# STM32_H750_POWER.net
KiCad netlist of a schematic drawn in Altium Designer
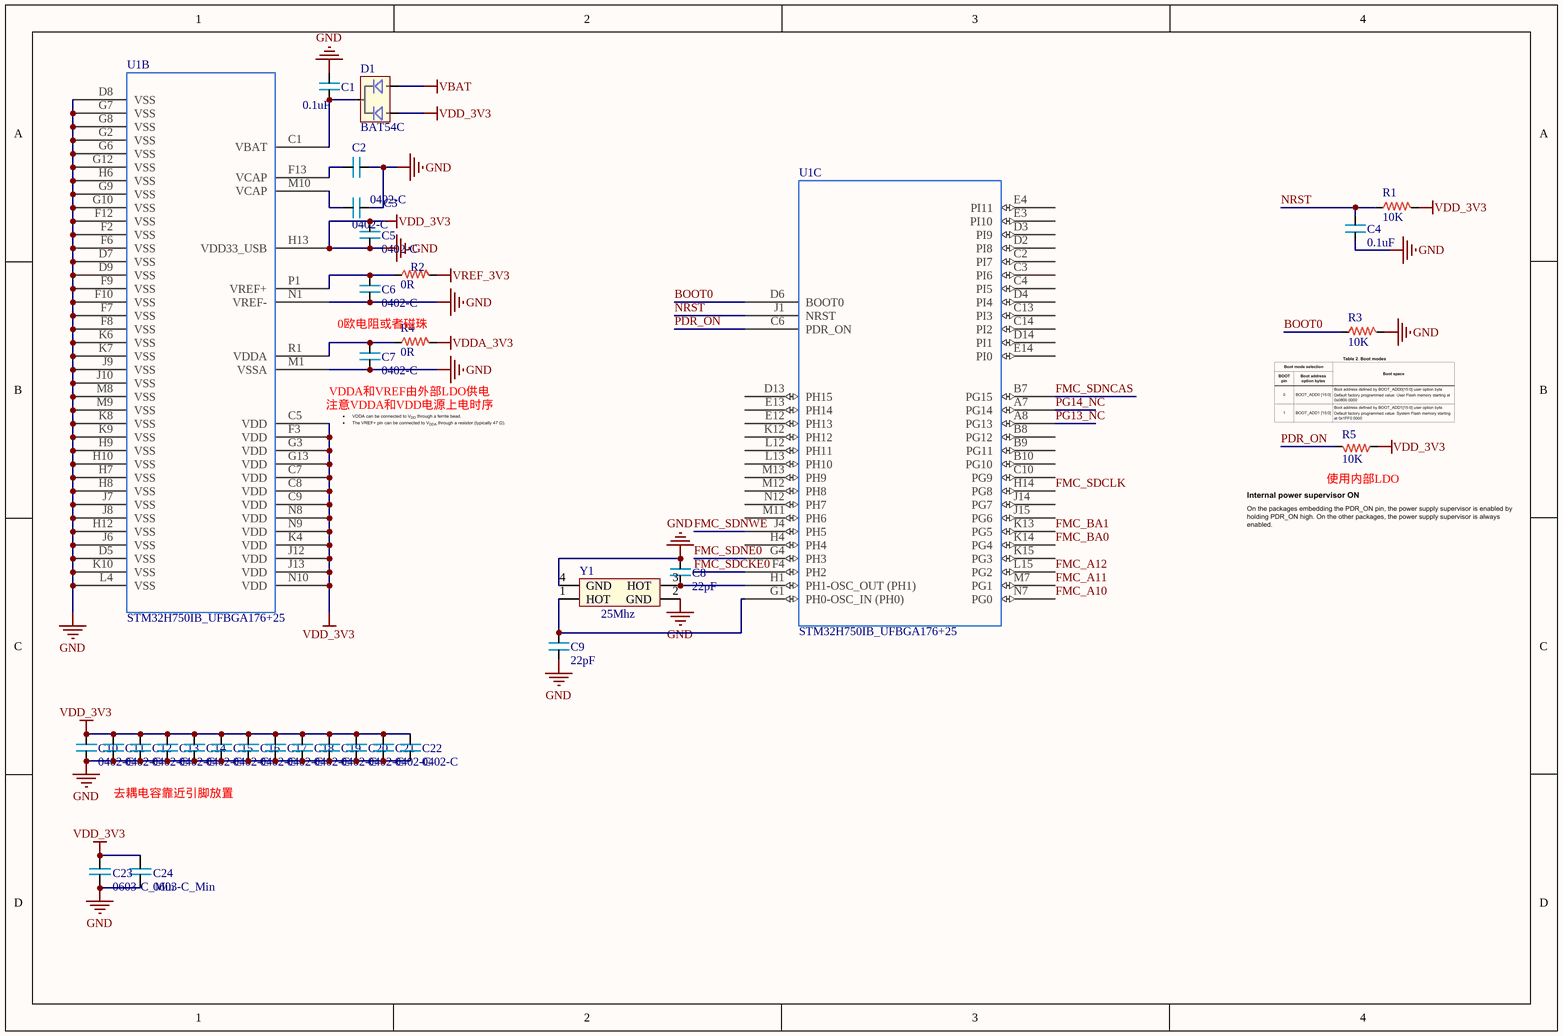
[diagram p0: STM32_H750_POWER.SchDoc]

(export (version "E")
  (design (tool "Eeschema 10.0.6"))
  (components
    (comp (ref "C1") (value "0.1uF") (footprint "0402") (libsource (lib "mcu") (part "0402-C")))
    (comp (ref "C2") (value "0402-C") (footprint "0402") (libsource (lib "mcu") (part "0402-C")))
    (comp (ref "C3") (value "0402-C") (footprint "0402") (libsource (lib "mcu") (part "0402-C")))
    (comp (ref "C4") (value "0.1uF") (footprint "0402") (libsource (lib "mcu") (part "0402-C")))
    (comp (ref "C5") (value "0402-C") (footprint "0402") (libsource (lib "mcu") (part "0402-C")))
    (comp (ref "C6") (value "0402-C") (footprint "0402") (libsource (lib "mcu") (part "0402-C")))
    (comp (ref "C7") (value "0402-C") (footprint "0402") (libsource (lib "mcu") (part "0402-C")))
    (comp (ref "C8") (value "22pF") (footprint "0402") (libsource (lib "mcu") (part "0402-C")))
    (comp (ref "C9") (value "22pF") (footprint "0402") (libsource (lib "mcu") (part "0402-C")))
    (comp (ref "C10") (value "0402-C") (footprint "0402") (libsource (lib "mcu") (part "0402-C")))
    (comp (ref "C11") (value "0402-C") (footprint "0402") (libsource (lib "mcu") (part "0402-C")))
    (comp (ref "C12") (value "0402-C") (footprint "0402") (libsource (lib "mcu") (part "0402-C")))
    (comp (ref "C13") (value "0402-C") (footprint "0402") (libsource (lib "mcu") (part "0402-C")))
    (comp (ref "C14") (value "0402-C") (footprint "0402") (libsource (lib "mcu") (part "0402-C")))
    (comp (ref "C15") (value "0402-C") (footprint "0402") (libsource (lib "mcu") (part "0402-C")))
    (comp (ref "C16") (value "0402-C") (footprint "0402") (libsource (lib "mcu") (part "0402-C")))
    (comp (ref "C17") (value "0402-C") (footprint "0402") (libsource (lib "mcu") (part "0402-C")))
    (comp (ref "C18") (value "0402-C") (footprint "0402") (libsource (lib "mcu") (part "0402-C")))
    (comp (ref "C19") (value "0402-C") (footprint "0402") (libsource (lib "mcu") (part "0402-C")))
    (comp (ref "C20") (value "0402-C") (footprint "0402") (libsource (lib "mcu") (part "0402-C")))
    (comp (ref "C21") (value "0402-C") (footprint "0402") (libsource (lib "mcu") (part "0402-C")))
    (comp (ref "C22") (value "0402-C") (footprint "0402") (libsource (lib "mcu") (part "0402-C")))
    (comp (ref "C23")
      (value "0603-C_Min")
      (footprint "0603P - 2")
      (libsource (lib "0718") (part "0603-C_Min"))
    )
    (comp (ref "C24")
      (value "0603-C_Min")
      (footprint "0603P - 2")
      (libsource (lib "0718") (part "0603-C_Min"))
    )
    (comp (ref "D1")
      (value "BAT54C")
      (footprint "SOT23-3")
      (description "双肖特基二极管")
      (libsource (lib "0718") (part "BAT54C"))
    )
    (comp (ref "R1") (value "10K") (footprint "0402") (libsource (lib "mcu") (part "0402-R")))
    (comp (ref "R2") (value "0R") (footprint "0402") (libsource (lib "mcu") (part "0402-R")))
    (comp (ref "R3") (value "10K") (footprint "0402") (libsource (lib "mcu") (part "0402-R")))
    (comp (ref "R4") (value "0R") (footprint "0402") (libsource (lib "mcu") (part "0402-R")))
    (comp (ref "R5") (value "10K") (footprint "0402") (libsource (lib "mcu") (part "0402-R")))
    (comp (ref "U1")
      (value "STM32H750IB_UFBGA176+25")
      (footprint "mcu:STM32H750IB_UFBGA176+25")
      (libsource (lib "") (part "STM32H750IB_UFBGA176+25_1"))
    )
    (comp (ref "Y1")
      (value "25Mhz")
      (footprint "XTAL3225")
      (description "3225贴片无源晶振")
      (libsource (lib "0718") (part "XTAL_3225"))
    )
  )
  (nets
    (net (code "1") (name "/BOOT0") (class "Default")
      (node (ref "R3") (pin "1") (pinfunction "1_1") (pintype "passive"))
      (node (ref "U1") (pin "D6") (pinfunction "BOOT0_D6") (pintype "power_in"))
    )
    (net (code "2") (name "/FMC_A10") (class "Default")
      (node (ref "U1") (pin "N7") (pinfunction "PG0_N7") (pintype "bidirectional"))
    )
    (net (code "3") (name "/FMC_A11") (class "Default")
      (node (ref "U1") (pin "M7") (pinfunction "PG1_M7") (pintype "bidirectional"))
    )
    (net (code "4") (name "/FMC_A12") (class "Default")
      (node (ref "U1") (pin "L15") (pinfunction "PG2_L15") (pintype "bidirectional"))
    )
    (net (code "5") (name "/FMC_BA0") (class "Default")
      (node (ref "U1") (pin "K14") (pinfunction "PG4_K14") (pintype "bidirectional"))
    )
    (net (code "6") (name "/FMC_BA1") (class "Default")
      (node (ref "U1") (pin "K13") (pinfunction "PG5_K13") (pintype "bidirectional"))
    )
    (net (code "7") (name "/FMC_SDCKE0") (class "Default")
      (node (ref "U1") (pin "F4") (pinfunction "PH2_F4") (pintype "bidirectional"))
    )
    (net (code "8") (name "/FMC_SDCLK") (class "Default")
      (node (ref "U1") (pin "H14") (pinfunction "PG8_H14") (pintype "bidirectional"))
    )
    (net (code "9") (name "/FMC_SDNCAS") (class "Default")
      (node (ref "U1") (pin "B7") (pinfunction "PG15_B7") (pintype "bidirectional"))
    )
    (net (code "10") (name "/FMC_SDNE0") (class "Default")
      (node (ref "U1") (pin "G4") (pinfunction "PH3_G4") (pintype "bidirectional"))
    )
    (net (code "11") (name "/FMC_SDNWE") (class "Default")
      (node (ref "U1") (pin "J4") (pinfunction "PH5_J4") (pintype "bidirectional"))
    )
    (net (code "12") (name "/NRST") (class "Default")
      (node (ref "C4") (pin "2") (pinfunction "2_2") (pintype "passive"))
      (node (ref "R1") (pin "1") (pinfunction "1_1") (pintype "passive"))
      (node (ref "U1") (pin "J1") (pinfunction "NRST_J1") (pintype "power_in"))
    )
    (net (code "13") (name "/PDR_ON") (class "Default")
      (node (ref "R5") (pin "2") (pinfunction "2_2") (pintype "passive"))
      (node (ref "U1") (pin "C6") (pinfunction "PDR_ON_C6") (pintype "power_in"))
    )
    (net (code "14") (name "/PG13_NC") (class "Default")
      (node (ref "U1") (pin "A8") (pinfunction "PG13_A8") (pintype "bidirectional"))
    )
    (net (code "15") (name "/PG14_NC") (class "Default")
      (node (ref "U1") (pin "A7") (pinfunction "PG14_A7") (pintype "bidirectional"))
    )
    (net (code "16") (name "GND") (class "Default")
      (node (ref "C1") (pin "2") (pinfunction "2_2") (pintype "passive"))
      (node (ref "C10") (pin "1") (pinfunction "1_1") (pintype "passive"))
      (node (ref "C10") (pin "2") (pinfunction "2_2") (pintype "passive"))
      (node (ref "C11") (pin "1") (pinfunction "1_1") (pintype "passive"))
      (node (ref "C11") (pin "2") (pinfunction "2_2") (pintype "passive"))
      (node (ref "C12") (pin "1") (pinfunction "1_1") (pintype "passive"))
      (node (ref "C12") (pin "2") (pinfunction "2_2") (pintype "passive"))
      (node (ref "C13") (pin "1") (pinfunction "1_1") (pintype "passive"))
      (node (ref "C13") (pin "2") (pinfunction "2_2") (pintype "passive"))
      (node (ref "C14") (pin "1") (pinfunction "1_1") (pintype "passive"))
      (node (ref "C14") (pin "2") (pinfunction "2_2") (pintype "passive"))
      (node (ref "C15") (pin "1") (pinfunction "1_1") (pintype "passive"))
      (node (ref "C15") (pin "2") (pinfunction "2_2") (pintype "passive"))
      (node (ref "C16") (pin "1") (pinfunction "1_1") (pintype "passive"))
      (node (ref "C16") (pin "2") (pinfunction "2_2") (pintype "passive"))
      (node (ref "C17") (pin "1") (pinfunction "1_1") (pintype "passive"))
      (node (ref "C17") (pin "2") (pinfunction "2_2") (pintype "passive"))
      (node (ref "C18") (pin "1") (pinfunction "1_1") (pintype "passive"))
      (node (ref "C18") (pin "2") (pinfunction "2_2") (pintype "passive"))
      (node (ref "C19") (pin "1") (pinfunction "1_1") (pintype "passive"))
      (node (ref "C19") (pin "2") (pinfunction "2_2") (pintype "passive"))
      (node (ref "C2") (pin "1") (pinfunction "1_1") (pintype "passive"))
      (node (ref "C20") (pin "1") (pinfunction "1_1") (pintype "passive"))
      (node (ref "C20") (pin "2") (pinfunction "2_2") (pintype "passive"))
      (node (ref "C21") (pin "1") (pinfunction "1_1") (pintype "passive"))
      (node (ref "C21") (pin "2") (pinfunction "2_2") (pintype "passive"))
      (node (ref "C22") (pin "1") (pinfunction "1_1") (pintype "passive"))
      (node (ref "C22") (pin "2") (pinfunction "2_2") (pintype "passive"))
      (node (ref "C23") (pin "1") (pinfunction "1_1") (pintype "passive"))
      (node (ref "C23") (pin "2") (pinfunction "2_2") (pintype "passive"))
      (node (ref "C24") (pin "1") (pinfunction "1_1") (pintype "passive"))
      (node (ref "C24") (pin "2") (pinfunction "2_2") (pintype "passive"))
      (node (ref "C3") (pin "2") (pinfunction "2_2") (pintype "passive"))
      (node (ref "C4") (pin "1") (pinfunction "1_1") (pintype "passive"))
      (node (ref "C5") (pin "1") (pinfunction "1_1") (pintype "passive"))
      (node (ref "C5") (pin "2") (pinfunction "2_2") (pintype "passive"))
      (node (ref "C6") (pin "1") (pinfunction "1_1") (pintype "passive"))
      (node (ref "C7") (pin "1") (pinfunction "1_1") (pintype "passive"))
      (node (ref "C8") (pin "2") (pinfunction "2_2") (pintype "passive"))
      (node (ref "C9") (pin "2") (pinfunction "2_2") (pintype "passive"))
      (node (ref "D1") (pin "1") (pintype "passive"))
      (node (ref "R1") (pin "2") (pinfunction "2_2") (pintype "passive"))
      (node (ref "R3") (pin "2") (pinfunction "2_2") (pintype "passive"))
      (node (ref "R5") (pin "1") (pinfunction "1_1") (pintype "passive"))
      (node (ref "U1") (pin "C5") (pinfunction "VDD_C5") (pintype "power_in"))
      (node (ref "U1") (pin "C7") (pinfunction "VDD_C7") (pintype "power_in"))
      (node (ref "U1") (pin "C8") (pinfunction "VDD_C8") (pintype "power_in"))
      (node (ref "U1") (pin "C9") (pinfunction "VDD_C9") (pintype "power_in"))
      (node (ref "U1") (pin "D5") (pinfunction "VSS_D5") (pintype "power_in"))
      (node (ref "U1") (pin "D7") (pinfunction "VSS_D7") (pintype "power_in"))
      (node (ref "U1") (pin "D8") (pinfunction "VSS_D8") (pintype "power_in"))
      (node (ref "U1") (pin "D9") (pinfunction "VSS_D9") (pintype "power_in"))
      (node (ref "U1") (pin "F10") (pinfunction "VSS_F10") (pintype "power_in"))
      (node (ref "U1") (pin "F12") (pinfunction "VSS_F12") (pintype "power_in"))
      (node (ref "U1") (pin "F2") (pinfunction "VSS_F2") (pintype "power_in"))
      (node (ref "U1") (pin "F3") (pinfunction "VDD_F3") (pintype "power_in"))
      (node (ref "U1") (pin "F6") (pinfunction "VSS_F6") (pintype "power_in"))
      (node (ref "U1") (pin "F7") (pinfunction "VSS_F7") (pintype "power_in"))
      (node (ref "U1") (pin "F8") (pinfunction "VSS_F8") (pintype "power_in"))
      (node (ref "U1") (pin "F9") (pinfunction "VSS_F9") (pintype "power_in"))
      (node (ref "U1") (pin "G10") (pinfunction "VSS_G10") (pintype "power_in"))
      (node (ref "U1") (pin "G12") (pinfunction "VSS_G12") (pintype "power_in"))
      (node (ref "U1") (pin "G13") (pinfunction "VDD_G13") (pintype "power_in"))
      (node (ref "U1") (pin "G2") (pinfunction "VSS_G2") (pintype "power_in"))
      (node (ref "U1") (pin "G3") (pinfunction "VDD_G3") (pintype "power_in"))
      (node (ref "U1") (pin "G6") (pinfunction "VSS_G6") (pintype "power_in"))
      (node (ref "U1") (pin "G7") (pinfunction "VSS_G7") (pintype "power_in"))
      (node (ref "U1") (pin "G8") (pinfunction "VSS_G8") (pintype "power_in"))
      (node (ref "U1") (pin "G9") (pinfunction "VSS_G9") (pintype "power_in"))
      (node (ref "U1") (pin "H10") (pinfunction "VSS_H10") (pintype "power_in"))
      (node (ref "U1") (pin "H12") (pinfunction "VSS_H12") (pintype "power_in"))
      (node (ref "U1") (pin "H13") (pinfunction "VDD33_USB_H13") (pintype "power_in"))
      (node (ref "U1") (pin "H6") (pinfunction "VSS_H6") (pintype "power_in"))
      (node (ref "U1") (pin "H7") (pinfunction "VSS_H7") (pintype "power_in"))
      (node (ref "U1") (pin "H8") (pinfunction "VSS_H8") (pintype "power_in"))
      (node (ref "U1") (pin "H9") (pinfunction "VSS_H9") (pintype "power_in"))
      (node (ref "U1") (pin "J10") (pinfunction "VSS_J10") (pintype "power_in"))
      (node (ref "U1") (pin "J12") (pinfunction "VDD_J12") (pintype "power_in"))
      (node (ref "U1") (pin "J13") (pinfunction "VDD_J13") (pintype "power_in"))
      (node (ref "U1") (pin "J6") (pinfunction "VSS_J6") (pintype "power_in"))
      (node (ref "U1") (pin "J7") (pinfunction "VSS_J7") (pintype "power_in"))
      (node (ref "U1") (pin "J8") (pinfunction "VSS_J8") (pintype "power_in"))
      (node (ref "U1") (pin "J9") (pinfunction "VSS_J9") (pintype "power_in"))
      (node (ref "U1") (pin "K10") (pinfunction "VSS_K10") (pintype "power_in"))
      (node (ref "U1") (pin "K4") (pinfunction "VDD_K4") (pintype "power_in"))
      (node (ref "U1") (pin "K6") (pinfunction "VSS_K6") (pintype "power_in"))
      (node (ref "U1") (pin "K7") (pinfunction "VSS_K7") (pintype "power_in"))
      (node (ref "U1") (pin "K8") (pinfunction "VSS_K8") (pintype "power_in"))
      (node (ref "U1") (pin "K9") (pinfunction "VSS_K9") (pintype "power_in"))
      (node (ref "U1") (pin "L4") (pinfunction "VSS_L4") (pintype "power_in"))
      (node (ref "U1") (pin "M1") (pinfunction "VSSA_M1") (pintype "power_in"))
      (node (ref "U1") (pin "M8") (pinfunction "VSS_M8") (pintype "power_in"))
      (node (ref "U1") (pin "M9") (pinfunction "VSS_M9") (pintype "power_in"))
      (node (ref "U1") (pin "N1") (pinfunction "VREF-_N1") (pintype "power_in"))
      (node (ref "U1") (pin "N10") (pinfunction "VDD_N10") (pintype "power_in"))
      (node (ref "U1") (pin "N8") (pinfunction "VDD_N8") (pintype "power_in"))
      (node (ref "U1") (pin "N9") (pinfunction "VDD_N9") (pintype "power_in"))
      (node (ref "Y1") (pin "2") (pinfunction "GND_2") (pintype "passive"))
      (node (ref "Y1") (pin "4") (pinfunction "GND_4") (pintype "passive"))
    )
    (net (code "17") (name "Net-(C2-Pad2)") (class "Default")
      (node (ref "C2") (pin "2") (pinfunction "2_2") (pintype "passive"))
      (node (ref "U1") (pin "F13") (pinfunction "VCAP_F13") (pintype "power_in"))
    )
    (net (code "18") (name "Net-(C3-Pad1)") (class "Default")
      (node (ref "C3") (pin "1") (pinfunction "1_1") (pintype "passive"))
      (node (ref "U1") (pin "M10") (pinfunction "VCAP_M10") (pintype "power_in"))
    )
    (net (code "19") (name "Net-(U1B-VBAT)") (class "Default")
      (node (ref "C1") (pin "1") (pinfunction "1_1") (pintype "passive"))
      (node (ref "D1") (pin "3") (pintype "passive"))
      (node (ref "U1") (pin "C1") (pinfunction "VBAT_C1") (pintype "power_in"))
    )
    (net (code "20") (name "Net-(U1B-VDDA)") (class "Default")
      (node (ref "C7") (pin "2") (pinfunction "2_2") (pintype "passive"))
      (node (ref "R4") (pin "1") (pinfunction "1_1") (pintype "passive"))
      (node (ref "U1") (pin "R1") (pinfunction "VDDA_R1") (pintype "power_in"))
    )
    (net (code "21") (name "Net-(U1B-VREF+)") (class "Default")
      (node (ref "C6") (pin "2") (pinfunction "2_2") (pintype "passive"))
      (node (ref "R2") (pin "1") (pinfunction "1_1") (pintype "passive"))
      (node (ref "U1") (pin "P1") (pinfunction "VREF+_P1") (pintype "power_in"))
    )
    (net (code "22") (name "Net-(U1C-PH0-OSC_IN_(PH0))") (class "Default")
      (node (ref "C9") (pin "1") (pinfunction "1_1") (pintype "passive"))
      (node (ref "U1") (pin "G1") (pinfunction "PH0-OSC_IN_(PH0)_G1") (pintype "bidirectional"))
      (node (ref "Y1") (pin "1") (pinfunction "HOT_1") (pintype "passive"))
    )
    (net (code "23") (name "Net-(U1C-PH1-OSC_OUT_(PH1))") (class "Default")
      (node (ref "C8") (pin "1") (pinfunction "1_1") (pintype "passive"))
      (node (ref "U1") (pin "H1") (pinfunction "PH1-OSC_OUT_(PH1)_H1") (pintype "bidirectional"))
      (node (ref "Y1") (pin "3") (pinfunction "HOT_3") (pintype "passive"))
    )
    (net (code "24") (name "VBAT") (class "Default") (node (ref "D1") (pin "2") (pintype "passive")))
    (net (code "25") (name "VDDA_3V3") (class "Default")
      (node (ref "R4") (pin "2") (pinfunction "2_2") (pintype "passive"))
    )
    (net (code "26") (name "VREF_3V3") (class "Default")
      (node (ref "R2") (pin "2") (pinfunction "2_2") (pintype "passive"))
    )
    (net (code "27") (name "unconnected-(U1C-PG3-PadK15)") (class "Default")
      (node (ref "U1") (pin "K15") (pinfunction "PG3_K15") (pintype "bidirectional"))
    )
    (net (code "28") (name "unconnected-(U1C-PG6-PadJ15)") (class "Default")
      (node (ref "U1") (pin "J15") (pinfunction "PG6_J15") (pintype "bidirectional"))
    )
    (net (code "29") (name "unconnected-(U1C-PG7-PadJ14)") (class "Default")
      (node (ref "U1") (pin "J14") (pinfunction "PG7_J14") (pintype "bidirectional"))
    )
    (net (code "30") (name "unconnected-(U1C-PG9-PadC10)") (class "Default")
      (node (ref "U1") (pin "C10") (pinfunction "PG9_C10") (pintype "bidirectional"))
    )
    (net (code "31") (name "unconnected-(U1C-PG10-PadB10)") (class "Default")
      (node (ref "U1") (pin "B10") (pinfunction "PG10_B10") (pintype "bidirectional"))
    )
    (net (code "32") (name "unconnected-(U1C-PG11-PadB9)") (class "Default")
      (node (ref "U1") (pin "B9") (pinfunction "PG11_B9") (pintype "bidirectional"))
    )
    (net (code "33") (name "unconnected-(U1C-PG12-PadB8)") (class "Default")
      (node (ref "U1") (pin "B8") (pinfunction "PG12_B8") (pintype "bidirectional"))
    )
    (net (code "34") (name "unconnected-(U1C-PH4-PadH4)") (class "Default")
      (node (ref "U1") (pin "H4") (pinfunction "PH4_H4") (pintype "bidirectional"))
    )
    (net (code "35") (name "unconnected-(U1C-PH6-PadM11)") (class "Default")
      (node (ref "U1") (pin "M11") (pinfunction "PH6_M11") (pintype "bidirectional"))
    )
    (net (code "36") (name "unconnected-(U1C-PH7-PadN12)") (class "Default")
      (node (ref "U1") (pin "N12") (pinfunction "PH7_N12") (pintype "bidirectional"))
    )
    (net (code "37") (name "unconnected-(U1C-PH8-PadM12)") (class "Default")
      (node (ref "U1") (pin "M12") (pinfunction "PH8_M12") (pintype "bidirectional"))
    )
    (net (code "38") (name "unconnected-(U1C-PH9-PadM13)") (class "Default")
      (node (ref "U1") (pin "M13") (pinfunction "PH9_M13") (pintype "bidirectional"))
    )
    (net (code "39") (name "unconnected-(U1C-PH10-PadL13)") (class "Default")
      (node (ref "U1") (pin "L13") (pinfunction "PH10_L13") (pintype "bidirectional"))
    )
    (net (code "40") (name "unconnected-(U1C-PH11-PadL12)") (class "Default")
      (node (ref "U1") (pin "L12") (pinfunction "PH11_L12") (pintype "bidirectional"))
    )
    (net (code "41") (name "unconnected-(U1C-PH12-PadK12)") (class "Default")
      (node (ref "U1") (pin "K12") (pinfunction "PH12_K12") (pintype "bidirectional"))
    )
    (net (code "42") (name "unconnected-(U1C-PH13-PadE12)") (class "Default")
      (node (ref "U1") (pin "E12") (pinfunction "PH13_E12") (pintype "bidirectional"))
    )
    (net (code "43") (name "unconnected-(U1C-PH14-PadE13)") (class "Default")
      (node (ref "U1") (pin "E13") (pinfunction "PH14_E13") (pintype "bidirectional"))
    )
    (net (code "44") (name "unconnected-(U1C-PH15-PadD13)") (class "Default")
      (node (ref "U1") (pin "D13") (pinfunction "PH15_D13") (pintype "bidirectional"))
    )
    (net (code "45") (name "unconnected-(U1C-PI0-PadE14)") (class "Default")
      (node (ref "U1") (pin "E14") (pinfunction "PI0_E14") (pintype "bidirectional"))
    )
    (net (code "46") (name "unconnected-(U1C-PI1-PadD14)") (class "Default")
      (node (ref "U1") (pin "D14") (pinfunction "PI1_D14") (pintype "bidirectional"))
    )
    (net (code "47") (name "unconnected-(U1C-PI2-PadC14)") (class "Default")
      (node (ref "U1") (pin "C14") (pinfunction "PI2_C14") (pintype "bidirectional"))
    )
    (net (code "48") (name "unconnected-(U1C-PI3-PadC13)") (class "Default")
      (node (ref "U1") (pin "C13") (pinfunction "PI3_C13") (pintype "bidirectional"))
    )
    (net (code "49") (name "unconnected-(U1C-PI4-PadD4)") (class "Default")
      (node (ref "U1") (pin "D4") (pinfunction "PI4_D4") (pintype "bidirectional"))
    )
    (net (code "50") (name "unconnected-(U1C-PI5-PadC4)") (class "Default")
      (node (ref "U1") (pin "C4") (pinfunction "PI5_C4") (pintype "bidirectional"))
    )
    (net (code "51") (name "unconnected-(U1C-PI6-PadC3)") (class "Default")
      (node (ref "U1") (pin "C3") (pinfunction "PI6_C3") (pintype "bidirectional"))
    )
    (net (code "52") (name "unconnected-(U1C-PI7-PadC2)") (class "Default")
      (node (ref "U1") (pin "C2") (pinfunction "PI7_C2") (pintype "bidirectional"))
    )
    (net (code "53") (name "unconnected-(U1C-PI8-PadD2)") (class "Default")
      (node (ref "U1") (pin "D2") (pinfunction "PI8_D2") (pintype "bidirectional"))
    )
    (net (code "54") (name "unconnected-(U1C-PI9-PadD3)") (class "Default")
      (node (ref "U1") (pin "D3") (pinfunction "PI9_D3") (pintype "bidirectional"))
    )
    (net (code "55") (name "unconnected-(U1C-PI10-PadE3)") (class "Default")
      (node (ref "U1") (pin "E3") (pinfunction "PI10_E3") (pintype "bidirectional"))
    )
    (net (code "56") (name "unconnected-(U1C-PI11-PadE4)") (class "Default")
      (node (ref "U1") (pin "E4") (pinfunction "PI11_E4") (pintype "bidirectional"))
    )
  )
)
